# SuperClock_Core_WIFI.net
KiCad netlist of a schematic drawn in Altium Designer
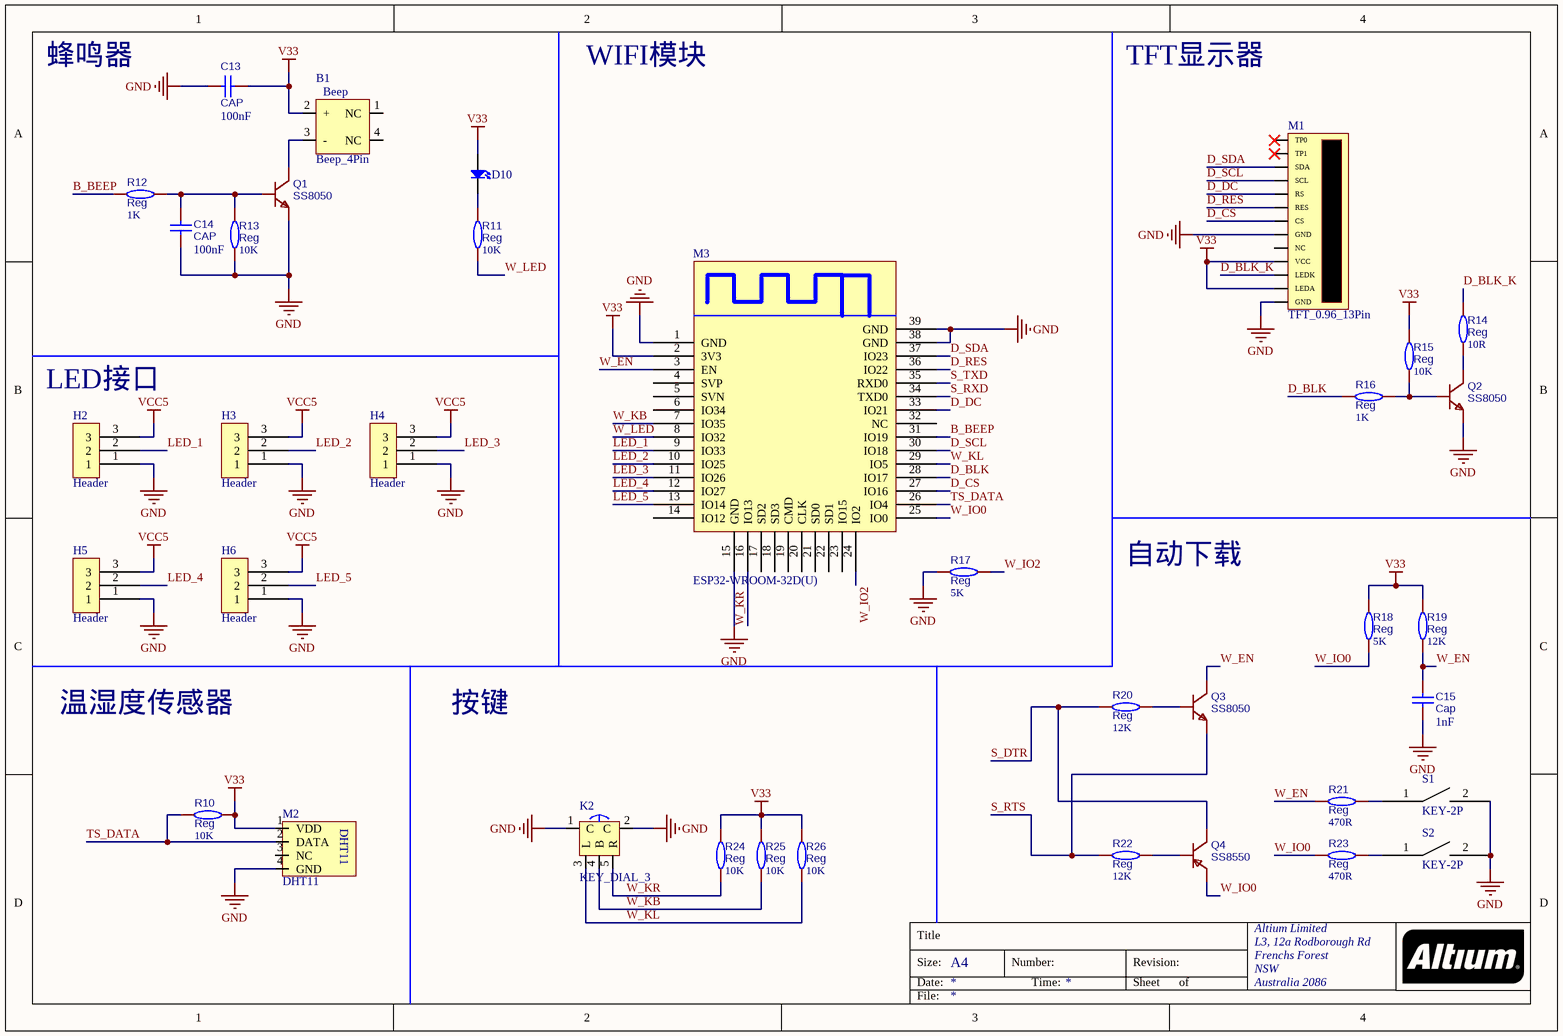
[diagram p0: SuperClock_Core_WIFI.SchDoc]

(export (version "E")
  (design (tool "Eeschema 10.0.6"))
  (components
    (comp (ref "B1")
      (value "Beep_4Pin")
      (footprint "Beep_4Pin_7525")
      (description "4Pin蜂鸣器")
      (libsource (lib "Levent_lib") (part "Beep_4Pin"))
    )
    (comp (ref "C13")
      (value "CAP")
      (footprint "C0603")
      (description "Cap")
      (fields
        (field (name "BOM_SUPPLIER PART") "C302008")
        (field (name "BOM_MANUFACTURER PART") "0603B103K101CT")
        (field (name "ALTIUM_VALUE") "100nF")
        (field (name "CONTRIBUTOR") "LCSC")
      )
      (libsource (lib "Levent_lib") (part "CAP"))
    )
    (comp (ref "C14")
      (value "CAP")
      (footprint "C0603")
      (description "Cap")
      (fields
        (field (name "BOM_SUPPLIER PART") "C302008")
        (field (name "BOM_MANUFACTURER PART") "0603B103K101CT")
        (field (name "ALTIUM_VALUE") "100nF")
        (field (name "CONTRIBUTOR") "LCSC")
      )
      (libsource (lib "Levent_lib") (part "CAP"))
    )
    (comp (ref "C15")
      (value "Cap")
      (footprint "C0603")
      (fields
        (field (name "BOM_SUPPLIER PART") "C302008")
        (field (name "BOM_MANUFACTURER PART") "0603B103K101CT")
        (field (name "ALTIUM_VALUE") "1nF")
        (field (name "CONTRIBUTOR") "LCSC")
      )
      (libsource (lib "Levent_lib") (part "CAP"))
    )
    (comp (ref "D10")
      (value "LED")
      (footprint "LED0603")
      (fields (field (name "PUBLISHER") "Altium Limited"))
      (libsource (lib "Levent_lib") (part "LED0"))
    )
    (comp (ref "H2")
      (value "Header")
      (footprint "H_2.54_P3")
      (description "3Pin接口")
      (libsource (lib "Levent_lib") (part "Header_P3"))
    )
    (comp (ref "H3")
      (value "Header")
      (footprint "H_2.54_P3")
      (description "3Pin接口")
      (libsource (lib "Levent_lib") (part "Header_P3"))
    )
    (comp (ref "H4")
      (value "Header")
      (footprint "H_2.54_P3")
      (description "3Pin接口")
      (libsource (lib "Levent_lib") (part "Header_P3"))
    )
    (comp (ref "H5")
      (value "Header")
      (footprint "H_2.54_P3")
      (description "3Pin接口")
      (libsource (lib "Levent_lib") (part "Header_P3"))
    )
    (comp (ref "H6")
      (value "Header")
      (footprint "H_2.54_P3")
      (description "3Pin接口")
      (libsource (lib "Levent_lib") (part "Header_P3"))
    )
    (comp (ref "K2")
      (value "KEY_DIAL_3")
      (footprint "KEY_DIAL_3")
      (description "3向拨轮开关")
      (libsource (lib "Levent_lib") (part "KEY_DIAL_3"))
    )
    (comp (ref "M1")
      (value "TFT_0.96_13Pin")
      (footprint "TFT_0.96_13Pin")
      (description "ST7735_TFT")
      (libsource (lib "Levent_lib") (part "TFT_0.96_13Pin"))
    )
    (comp (ref "M2")
      (value "DHT11")
      (footprint "SENSOR-TH_DHT11-HOR")
      (description "温湿度传感器")
      (libsource (lib "Levent_lib") (part "DHT11"))
    )
    (comp (ref "M3")
      (value "ESP32-WROOM-32D(U)")
      (footprint "ESP32-WROOM-32D")
      (libsource (lib "Levent_lib") (part "ESP32-WROOM-32D(U)"))
    )
    (comp (ref "Q1")
      (value "SS8050")
      (footprint "SOT-23-3")
      (description "NPN")
      (fields (field (name "BOM_SUPPLIER PART") "C541705") (field (name "CONTRIBUTOR") "LCSC"))
      (libsource (lib "Levent_lib") (part "SS8050"))
    )
    (comp (ref "Q2")
      (value "SS8050")
      (footprint "SOT-23-3")
      (description "NPN")
      (fields (field (name "BOM_SUPPLIER PART") "C541705") (field (name "CONTRIBUTOR") "LCSC"))
      (libsource (lib "Levent_lib") (part "SS8050"))
    )
    (comp (ref "Q3")
      (value "SS8050")
      (footprint "SOT-23-3")
      (description "NPN")
      (fields (field (name "BOM_SUPPLIER PART") "C541705") (field (name "CONTRIBUTOR") "LCSC"))
      (libsource (lib "Levent_lib") (part "SS8050"))
    )
    (comp (ref "Q4")
      (value "SS8550")
      (footprint "SOT-23-3")
      (description "PNP")
      (fields (field (name "BOM_SUPPLIER PART") "C541706") (field (name "CONTRIBUTOR") "LCSC"))
      (libsource (lib "Levent_lib") (part "SS8550"))
    )
    (comp (ref "R10")
      (value "Reg")
      (footprint "R0603")
      (description "电阻")
      (fields
        (field (name "BOM_SUPPLIER PART") "C465721")
        (field (name "BOM_MANUFACTURER PART") "AR03BTCX1002A")
        (field (name "ALTIUM_VALUE") "10K")
        (field (name "CONTRIBUTOR") "LCSC")
      )
      (libsource (lib "Levent_lib") (part "Res"))
    )
    (comp (ref "R11")
      (value "Reg")
      (footprint "R0603")
      (description "电阻")
      (fields
        (field (name "BOM_SUPPLIER PART") "C465721")
        (field (name "BOM_MANUFACTURER PART") "AR03BTCX1002A")
        (field (name "ALTIUM_VALUE") "10K")
        (field (name "CONTRIBUTOR") "LCSC")
      )
      (libsource (lib "Levent_lib") (part "Res"))
    )
    (comp (ref "R12")
      (value "Reg")
      (footprint "R0603")
      (description "电阻")
      (fields
        (field (name "BOM_SUPPLIER PART") "C465721")
        (field (name "BOM_MANUFACTURER PART") "AR03BTCX1002A")
        (field (name "ALTIUM_VALUE") "1K")
        (field (name "CONTRIBUTOR") "LCSC")
      )
      (libsource (lib "Levent_lib") (part "Res"))
    )
    (comp (ref "R13")
      (value "Reg")
      (footprint "R0603")
      (description "电阻")
      (fields
        (field (name "BOM_SUPPLIER PART") "C465721")
        (field (name "BOM_MANUFACTURER PART") "AR03BTCX1002A")
        (field (name "ALTIUM_VALUE") "10K")
        (field (name "CONTRIBUTOR") "LCSC")
      )
      (libsource (lib "Levent_lib") (part "Res"))
    )
    (comp (ref "R14")
      (value "Reg")
      (footprint "R0603")
      (description "电阻")
      (fields
        (field (name "BOM_SUPPLIER PART") "C465721")
        (field (name "BOM_MANUFACTURER PART") "AR03BTCX1002A")
        (field (name "ALTIUM_VALUE") "10R")
        (field (name "CONTRIBUTOR") "LCSC")
      )
      (libsource (lib "Levent_lib") (part "Res"))
    )
    (comp (ref "R15")
      (value "Reg")
      (footprint "R0603")
      (description "电阻")
      (fields
        (field (name "BOM_SUPPLIER PART") "C465721")
        (field (name "BOM_MANUFACTURER PART") "AR03BTCX1002A")
        (field (name "ALTIUM_VALUE") "10K")
        (field (name "CONTRIBUTOR") "LCSC")
      )
      (libsource (lib "Levent_lib") (part "Res"))
    )
    (comp (ref "R16")
      (value "Reg")
      (footprint "R0603")
      (description "电阻")
      (fields
        (field (name "BOM_SUPPLIER PART") "C465721")
        (field (name "BOM_MANUFACTURER PART") "AR03BTCX1002A")
        (field (name "ALTIUM_VALUE") "1K")
        (field (name "CONTRIBUTOR") "LCSC")
      )
      (libsource (lib "Levent_lib") (part "Res"))
    )
    (comp (ref "R17")
      (value "Reg")
      (footprint "R0603")
      (description "电阻")
      (fields
        (field (name "BOM_SUPPLIER PART") "C465721")
        (field (name "BOM_MANUFACTURER PART") "AR03BTCX1002A")
        (field (name "ALTIUM_VALUE") "5K")
        (field (name "CONTRIBUTOR") "LCSC")
      )
      (libsource (lib "Levent_lib") (part "Res"))
    )
    (comp (ref "R18")
      (value "Reg")
      (footprint "R0603")
      (description "电阻")
      (fields
        (field (name "BOM_SUPPLIER PART") "C465721")
        (field (name "BOM_MANUFACTURER PART") "AR03BTCX1002A")
        (field (name "ALTIUM_VALUE") "5K")
        (field (name "CONTRIBUTOR") "LCSC")
      )
      (libsource (lib "Levent_lib") (part "Res"))
    )
    (comp (ref "R19")
      (value "Reg")
      (footprint "R0603")
      (description "电阻")
      (fields
        (field (name "BOM_SUPPLIER PART") "C465721")
        (field (name "BOM_MANUFACTURER PART") "AR03BTCX1002A")
        (field (name "ALTIUM_VALUE") "12K")
        (field (name "CONTRIBUTOR") "LCSC")
      )
      (libsource (lib "Levent_lib") (part "Res"))
    )
    (comp (ref "R20")
      (value "Reg")
      (footprint "R0603")
      (description "电阻")
      (fields
        (field (name "BOM_SUPPLIER PART") "C465721")
        (field (name "BOM_MANUFACTURER PART") "AR03BTCX1002A")
        (field (name "ALTIUM_VALUE") "12K")
        (field (name "CONTRIBUTOR") "LCSC")
      )
      (libsource (lib "Levent_lib") (part "Res"))
    )
    (comp (ref "R21")
      (value "Reg")
      (footprint "R0603")
      (description "电阻")
      (fields
        (field (name "BOM_SUPPLIER PART") "C465721")
        (field (name "BOM_MANUFACTURER PART") "AR03BTCX1002A")
        (field (name "ALTIUM_VALUE") "470R")
        (field (name "CONTRIBUTOR") "LCSC")
      )
      (libsource (lib "Levent_lib") (part "Res"))
    )
    (comp (ref "R22")
      (value "Reg")
      (footprint "R0603")
      (description "电阻")
      (fields
        (field (name "BOM_SUPPLIER PART") "C465721")
        (field (name "BOM_MANUFACTURER PART") "AR03BTCX1002A")
        (field (name "ALTIUM_VALUE") "12K")
        (field (name "CONTRIBUTOR") "LCSC")
      )
      (libsource (lib "Levent_lib") (part "Res"))
    )
    (comp (ref "R23")
      (value "Reg")
      (footprint "R0603")
      (description "电阻")
      (fields
        (field (name "BOM_SUPPLIER PART") "C465721")
        (field (name "BOM_MANUFACTURER PART") "AR03BTCX1002A")
        (field (name "ALTIUM_VALUE") "470R")
        (field (name "CONTRIBUTOR") "LCSC")
      )
      (libsource (lib "Levent_lib") (part "Res"))
    )
    (comp (ref "R24")
      (value "Reg")
      (footprint "R0603")
      (description "电阻")
      (fields
        (field (name "BOM_SUPPLIER PART") "C465721")
        (field (name "BOM_MANUFACTURER PART") "AR03BTCX1002A")
        (field (name "ALTIUM_VALUE") "10K")
        (field (name "CONTRIBUTOR") "LCSC")
      )
      (libsource (lib "Levent_lib") (part "Res"))
    )
    (comp (ref "R25")
      (value "Reg")
      (footprint "R0603")
      (description "电阻")
      (fields
        (field (name "BOM_SUPPLIER PART") "C465721")
        (field (name "BOM_MANUFACTURER PART") "AR03BTCX1002A")
        (field (name "ALTIUM_VALUE") "10K")
        (field (name "CONTRIBUTOR") "LCSC")
      )
      (libsource (lib "Levent_lib") (part "Res"))
    )
    (comp (ref "R26")
      (value "Reg")
      (footprint "R0603")
      (description "电阻")
      (fields
        (field (name "BOM_SUPPLIER PART") "C465721")
        (field (name "BOM_MANUFACTURER PART") "AR03BTCX1002A")
        (field (name "ALTIUM_VALUE") "10K")
        (field (name "CONTRIBUTOR") "LCSC")
      )
      (libsource (lib "Levent_lib") (part "Res"))
    )
    (comp (ref "S1")
      (value "KEY-2P")
      (footprint "KEY_SOT_P2")
      (description "KEY-2Pp")
      (libsource (lib "Levent_lib") (part "KEY_2P"))
    )
    (comp (ref "S2")
      (value "KEY-2P")
      (footprint "KEY_SOT_P2")
      (description "KEY-2Pp")
      (libsource (lib "Levent_lib") (part "KEY_2P"))
    )
  )
  (nets
    (net (code "1") (name "/B_BEEP") (class "Default")
      (node (ref "M3") (pin "31") (pinfunction "IO19_31") (pintype "passive"))
      (node (ref "R12") (pin "2") (pinfunction "2_2") (pintype "passive"))
    )
    (net (code "2") (name "/D_BLK") (class "Default")
      (node (ref "M3") (pin "28") (pinfunction "IO17_28") (pintype "passive"))
      (node (ref "R16") (pin "2") (pinfunction "2_2") (pintype "passive"))
    )
    (net (code "3") (name "/D_BLK_K") (class "Default")
      (node (ref "M1") (pin "11") (pinfunction "LEDK_11") (pintype "passive"))
      (node (ref "R14") (pin "2") (pinfunction "2_2") (pintype "passive"))
    )
    (net (code "4") (name "/D_CS") (class "Default")
      (node (ref "M1") (pin "7") (pinfunction "CS_7") (pintype "passive"))
      (node (ref "M3") (pin "27") (pinfunction "IO16_27") (pintype "passive"))
    )
    (net (code "5") (name "/D_DC") (class "Default")
      (node (ref "M1") (pin "5") (pinfunction "RS_5") (pintype "passive"))
      (node (ref "M3") (pin "33") (pinfunction "IO21_33") (pintype "passive"))
    )
    (net (code "6") (name "/D_RES") (class "Default")
      (node (ref "M1") (pin "6") (pinfunction "RES_6") (pintype "passive"))
      (node (ref "M3") (pin "36") (pinfunction "IO22_36") (pintype "passive"))
    )
    (net (code "7") (name "/D_SCL") (class "Default")
      (node (ref "M1") (pin "4") (pinfunction "SCL_4") (pintype "passive"))
      (node (ref "M3") (pin "30") (pinfunction "IO18_30") (pintype "passive"))
    )
    (net (code "8") (name "/D_SDA") (class "Default")
      (node (ref "M1") (pin "3") (pinfunction "SDA_3") (pintype "passive"))
      (node (ref "M3") (pin "37") (pinfunction "IO23_37") (pintype "passive"))
    )
    (net (code "9") (name "/LED_1") (class "Default")
      (node (ref "H2") (pin "2") (pinfunction "2_2") (pintype "passive"))
      (node (ref "M3") (pin "9") (pinfunction "IO33_9") (pintype "passive"))
    )
    (net (code "10") (name "/LED_2") (class "Default")
      (node (ref "H3") (pin "2") (pinfunction "2_2") (pintype "passive"))
      (node (ref "M3") (pin "10") (pinfunction "IO25_10") (pintype "passive"))
    )
    (net (code "11") (name "/LED_3") (class "Default")
      (node (ref "H4") (pin "2") (pinfunction "2_2") (pintype "passive"))
      (node (ref "M3") (pin "11") (pinfunction "IO26_11") (pintype "passive"))
    )
    (net (code "12") (name "/LED_4") (class "Default")
      (node (ref "H5") (pin "2") (pinfunction "2_2") (pintype "passive"))
      (node (ref "M3") (pin "12") (pinfunction "IO27_12") (pintype "passive"))
    )
    (net (code "13") (name "/LED_5") (class "Default")
      (node (ref "H6") (pin "2") (pinfunction "2_2") (pintype "passive"))
      (node (ref "M3") (pin "13") (pinfunction "IO14_13") (pintype "passive"))
    )
    (net (code "14") (name "/S_DTR") (class "Default")
      (node (ref "Q4") (pin "3") (pinfunction "C_3") (pintype "passive"))
      (node (ref "R20") (pin "2") (pinfunction "2_2") (pintype "passive"))
    )
    (net (code "15") (name "/S_RTS") (class "Default")
      (node (ref "Q3") (pin "2") (pinfunction "E_2") (pintype "passive"))
      (node (ref "R22") (pin "2") (pinfunction "2_2") (pintype "passive"))
    )
    (net (code "16") (name "/S_RXD") (class "Default")
      (node (ref "M3") (pin "34") (pinfunction "TXD0_34") (pintype "passive"))
    )
    (net (code "17") (name "/S_TXD") (class "Default")
      (node (ref "M3") (pin "35") (pinfunction "RXD0_35") (pintype "passive"))
    )
    (net (code "18") (name "/TS_DATA") (class "Default")
      (node (ref "M2") (pin "2") (pinfunction "DATA_2") (pintype "passive"))
      (node (ref "M3") (pin "26") (pinfunction "IO4_26") (pintype "passive"))
      (node (ref "R10") (pin "2") (pinfunction "2_2") (pintype "passive"))
    )
    (net (code "19") (name "/W_EN") (class "Default")
      (node (ref "C15") (pin "1") (pinfunction "1_1") (pintype "passive"))
      (node (ref "M3") (pin "3") (pinfunction "EN_3") (pintype "passive"))
      (node (ref "Q3") (pin "3") (pinfunction "C_3") (pintype "passive"))
      (node (ref "R19") (pin "1") (pinfunction "1_1") (pintype "passive"))
      (node (ref "R21") (pin "2") (pinfunction "2_2") (pintype "passive"))
    )
    (net (code "20") (name "/W_IO0") (class "Default")
      (node (ref "M3") (pin "25") (pinfunction "IO0_25") (pintype "passive"))
      (node (ref "Q4") (pin "2") (pinfunction "E_2") (pintype "passive"))
      (node (ref "R18") (pin "1") (pinfunction "1_1") (pintype "passive"))
      (node (ref "R23") (pin "2") (pinfunction "2_2") (pintype "passive"))
    )
    (net (code "21") (name "/W_IO2") (class "Default")
      (node (ref "M3") (pin "24") (pinfunction "IO2_24") (pintype "passive"))
      (node (ref "R17") (pin "1") (pinfunction "1_1") (pintype "passive"))
    )
    (net (code "22") (name "/W_KB") (class "Default")
      (node (ref "K2") (pin "4") (pinfunction "B_4") (pintype "passive"))
      (node (ref "M3") (pin "7") (pinfunction "IO35_7") (pintype "passive"))
      (node (ref "R25") (pin "2") (pinfunction "2_2") (pintype "passive"))
    )
    (net (code "23") (name "/W_KL") (class "Default")
      (node (ref "K2") (pin "3") (pinfunction "L_3") (pintype "passive"))
      (node (ref "M3") (pin "29") (pinfunction "IO5_29") (pintype "passive"))
      (node (ref "R26") (pin "2") (pinfunction "2_2") (pintype "passive"))
    )
    (net (code "24") (name "/W_KR") (class "Default")
      (node (ref "K2") (pin "5") (pinfunction "R_5") (pintype "passive"))
      (node (ref "M3") (pin "16") (pinfunction "IO13_16") (pintype "passive"))
      (node (ref "R24") (pin "2") (pinfunction "2_2") (pintype "passive"))
    )
    (net (code "25") (name "/W_LED") (class "Default")
      (node (ref "M3") (pin "8") (pinfunction "IO32_8") (pintype "passive"))
      (node (ref "R11") (pin "1") (pinfunction "1_1") (pintype "passive"))
    )
    (net (code "26") (name "GND") (class "Default")
      (node (ref "C13") (pin "1") (pinfunction "1_1") (pintype "passive"))
      (node (ref "C14") (pin "2") (pinfunction "2_2") (pintype "passive"))
      (node (ref "C15") (pin "2") (pinfunction "2_2") (pintype "passive"))
      (node (ref "H2") (pin "1") (pinfunction "1_1") (pintype "passive"))
      (node (ref "H3") (pin "1") (pinfunction "1_1") (pintype "passive"))
      (node (ref "H4") (pin "1") (pinfunction "1_1") (pintype "passive"))
      (node (ref "H5") (pin "1") (pinfunction "1_1") (pintype "passive"))
      (node (ref "H6") (pin "1") (pinfunction "1_1") (pintype "passive"))
      (node (ref "K2") (pin "1") (pinfunction "C_1") (pintype "passive"))
      (node (ref "K2") (pin "2") (pinfunction "C_2") (pintype "passive"))
      (node (ref "M1") (pin "13") (pinfunction "GND_13") (pintype "passive"))
      (node (ref "M1") (pin "8") (pinfunction "GND_8") (pintype "passive"))
      (node (ref "M2") (pin "4") (pinfunction "GND_4") (pintype "passive"))
      (node (ref "M3") (pin "1") (pinfunction "GND_1") (pintype "passive"))
      (node (ref "M3") (pin "15") (pinfunction "GND_15") (pintype "passive"))
      (node (ref "M3") (pin "38") (pinfunction "GND_38") (pintype "passive"))
      (node (ref "M3") (pin "39") (pinfunction "GND_39") (pintype "passive"))
      (node (ref "Q1") (pin "2") (pinfunction "E_2") (pintype "passive"))
      (node (ref "Q2") (pin "2") (pinfunction "E_2") (pintype "passive"))
      (node (ref "R13") (pin "2") (pinfunction "2_2") (pintype "passive"))
      (node (ref "R17") (pin "2") (pinfunction "2_2") (pintype "passive"))
      (node (ref "S1") (pin "2") (pinfunction "2_2") (pintype "passive"))
      (node (ref "S2") (pin "2") (pinfunction "2_2") (pintype "passive"))
    )
    (net (code "27") (name "Net-(B1--)") (class "Default")
      (node (ref "B1") (pin "3") (pinfunction "-_3") (pintype "passive"))
      (node (ref "Q1") (pin "3") (pinfunction "C_3") (pintype "passive"))
    )
    (net (code "28") (name "Net-(D10-K)") (class "Default")
      (node (ref "D10") (pin "1") (pinfunction "K_1") (pintype "passive"))
      (node (ref "R11") (pin "2") (pinfunction "2_2") (pintype "passive"))
    )
    (net (code "29") (name "Net-(Q1-B)") (class "Default")
      (node (ref "C14") (pin "1") (pinfunction "1_1") (pintype "passive"))
      (node (ref "Q1") (pin "1") (pinfunction "B_1") (pintype "passive"))
      (node (ref "R12") (pin "1") (pinfunction "1_1") (pintype "passive"))
      (node (ref "R13") (pin "1") (pinfunction "1_1") (pintype "passive"))
    )
    (net (code "30") (name "Net-(Q2-B)") (class "Default")
      (node (ref "Q2") (pin "1") (pinfunction "B_1") (pintype "passive"))
      (node (ref "R15") (pin "1") (pinfunction "1_1") (pintype "passive"))
      (node (ref "R16") (pin "1") (pinfunction "1_1") (pintype "passive"))
    )
    (net (code "31") (name "Net-(Q2-C)") (class "Default")
      (node (ref "Q2") (pin "3") (pinfunction "C_3") (pintype "passive"))
      (node (ref "R14") (pin "1") (pinfunction "1_1") (pintype "passive"))
    )
    (net (code "32") (name "Net-(Q3-B)") (class "Default")
      (node (ref "Q3") (pin "1") (pinfunction "B_1") (pintype "passive"))
      (node (ref "R20") (pin "1") (pinfunction "1_1") (pintype "passive"))
    )
    (net (code "33") (name "Net-(Q4-B)") (class "Default")
      (node (ref "Q4") (pin "1") (pinfunction "B_1") (pintype "passive"))
      (node (ref "R22") (pin "1") (pinfunction "1_1") (pintype "passive"))
    )
    (net (code "34") (name "Net-(R21-Pad1)") (class "Default")
      (node (ref "R21") (pin "1") (pinfunction "1_1") (pintype "passive"))
      (node (ref "S1") (pin "1") (pinfunction "1_1") (pintype "passive"))
    )
    (net (code "35") (name "Net-(R23-Pad1)") (class "Default")
      (node (ref "R23") (pin "1") (pinfunction "1_1") (pintype "passive"))
      (node (ref "S2") (pin "1") (pinfunction "1_1") (pintype "passive"))
    )
    (net (code "36") (name "V33") (class "Default")
      (node (ref "B1") (pin "2") (pinfunction "+_2") (pintype "passive"))
      (node (ref "C13") (pin "2") (pinfunction "2_2") (pintype "passive"))
      (node (ref "D10") (pin "2") (pinfunction "A_2") (pintype "passive"))
      (node (ref "M1") (pin "10") (pinfunction "VCC_10") (pintype "passive"))
      (node (ref "M1") (pin "12") (pinfunction "LEDA_12") (pintype "passive"))
      (node (ref "M2") (pin "1") (pinfunction "VDD_1") (pintype "passive"))
      (node (ref "M3") (pin "2") (pinfunction "3V3_2") (pintype "passive"))
      (node (ref "R10") (pin "1") (pinfunction "1_1") (pintype "passive"))
      (node (ref "R15") (pin "2") (pinfunction "2_2") (pintype "passive"))
      (node (ref "R18") (pin "2") (pinfunction "2_2") (pintype "passive"))
      (node (ref "R19") (pin "2") (pinfunction "2_2") (pintype "passive"))
      (node (ref "R24") (pin "1") (pinfunction "1_1") (pintype "passive"))
      (node (ref "R25") (pin "1") (pinfunction "1_1") (pintype "passive"))
      (node (ref "R26") (pin "1") (pinfunction "1_1") (pintype "passive"))
    )
    (net (code "37") (name "VCC5") (class "Default")
      (node (ref "H2") (pin "3") (pinfunction "3_3") (pintype "passive"))
      (node (ref "H3") (pin "3") (pinfunction "3_3") (pintype "passive"))
      (node (ref "H4") (pin "3") (pinfunction "3_3") (pintype "passive"))
      (node (ref "H5") (pin "3") (pinfunction "3_3") (pintype "passive"))
      (node (ref "H6") (pin "3") (pinfunction "3_3") (pintype "passive"))
    )
    (net (code "38") (name "unconnected-(B1-NC-Pad1)") (class "Default")
      (node (ref "B1") (pin "1") (pinfunction "NC_1") (pintype "passive"))
    )
    (net (code "39") (name "unconnected-(B1-NC-Pad4)") (class "Default")
      (node (ref "B1") (pin "4") (pinfunction "NC_4") (pintype "passive"))
    )
    (net (code "40") (name "unconnected-(M1-NC-Pad9)") (class "Default")
      (node (ref "M1") (pin "9") (pinfunction "NC_9") (pintype "passive"))
    )
    (net (code "41") (name "unconnected-(M1-TP0-Pad1)") (class "Default")
      (node (ref "M1") (pin "1") (pinfunction "TP0_1") (pintype "passive+no_connect"))
    )
    (net (code "42") (name "unconnected-(M1-TP1-Pad2)") (class "Default")
      (node (ref "M1") (pin "2") (pinfunction "TP1_2") (pintype "passive+no_connect"))
    )
    (net (code "43") (name "unconnected-(M2-NC-Pad3)") (class "Default")
      (node (ref "M2") (pin "3") (pinfunction "NC_3") (pintype "passive"))
    )
    (net (code "44") (name "unconnected-(M3-CLK-Pad20)") (class "Default")
      (node (ref "M3") (pin "20") (pinfunction "CLK_20") (pintype "passive"))
    )
    (net (code "45") (name "unconnected-(M3-CMD-Pad19)") (class "Default")
      (node (ref "M3") (pin "19") (pinfunction "CMD_19") (pintype "passive"))
    )
    (net (code "46") (name "unconnected-(M3-IO12-Pad14)") (class "Default")
      (node (ref "M3") (pin "14") (pinfunction "IO12_14") (pintype "passive"))
    )
    (net (code "47") (name "unconnected-(M3-IO15-Pad23)") (class "Default")
      (node (ref "M3") (pin "23") (pinfunction "IO15_23") (pintype "passive"))
    )
    (net (code "48") (name "unconnected-(M3-IO34-Pad6)") (class "Default")
      (node (ref "M3") (pin "6") (pinfunction "IO34_6") (pintype "passive"))
    )
    (net (code "49") (name "unconnected-(M3-NC-Pad32)") (class "Default")
      (node (ref "M3") (pin "32") (pinfunction "NC_32") (pintype "passive"))
    )
    (net (code "50") (name "unconnected-(M3-SD0-Pad21)") (class "Default")
      (node (ref "M3") (pin "21") (pinfunction "SD0_21") (pintype "passive"))
    )
    (net (code "51") (name "unconnected-(M3-SD1-Pad22)") (class "Default")
      (node (ref "M3") (pin "22") (pinfunction "SD1_22") (pintype "passive"))
    )
    (net (code "52") (name "unconnected-(M3-SD2-Pad17)") (class "Default")
      (node (ref "M3") (pin "17") (pinfunction "SD2_17") (pintype "passive"))
    )
    (net (code "53") (name "unconnected-(M3-SD3-Pad18)") (class "Default")
      (node (ref "M3") (pin "18") (pinfunction "SD3_18") (pintype "passive"))
    )
    (net (code "54") (name "unconnected-(M3-SVN-Pad5)") (class "Default")
      (node (ref "M3") (pin "5") (pinfunction "SVN_5") (pintype "passive"))
    )
    (net (code "55") (name "unconnected-(M3-SVP-Pad4)") (class "Default")
      (node (ref "M3") (pin "4") (pinfunction "SVP_4") (pintype "passive"))
    )
  )
)
